# Sheet1.net
KiCad netlist of a schematic drawn in Altium Designer
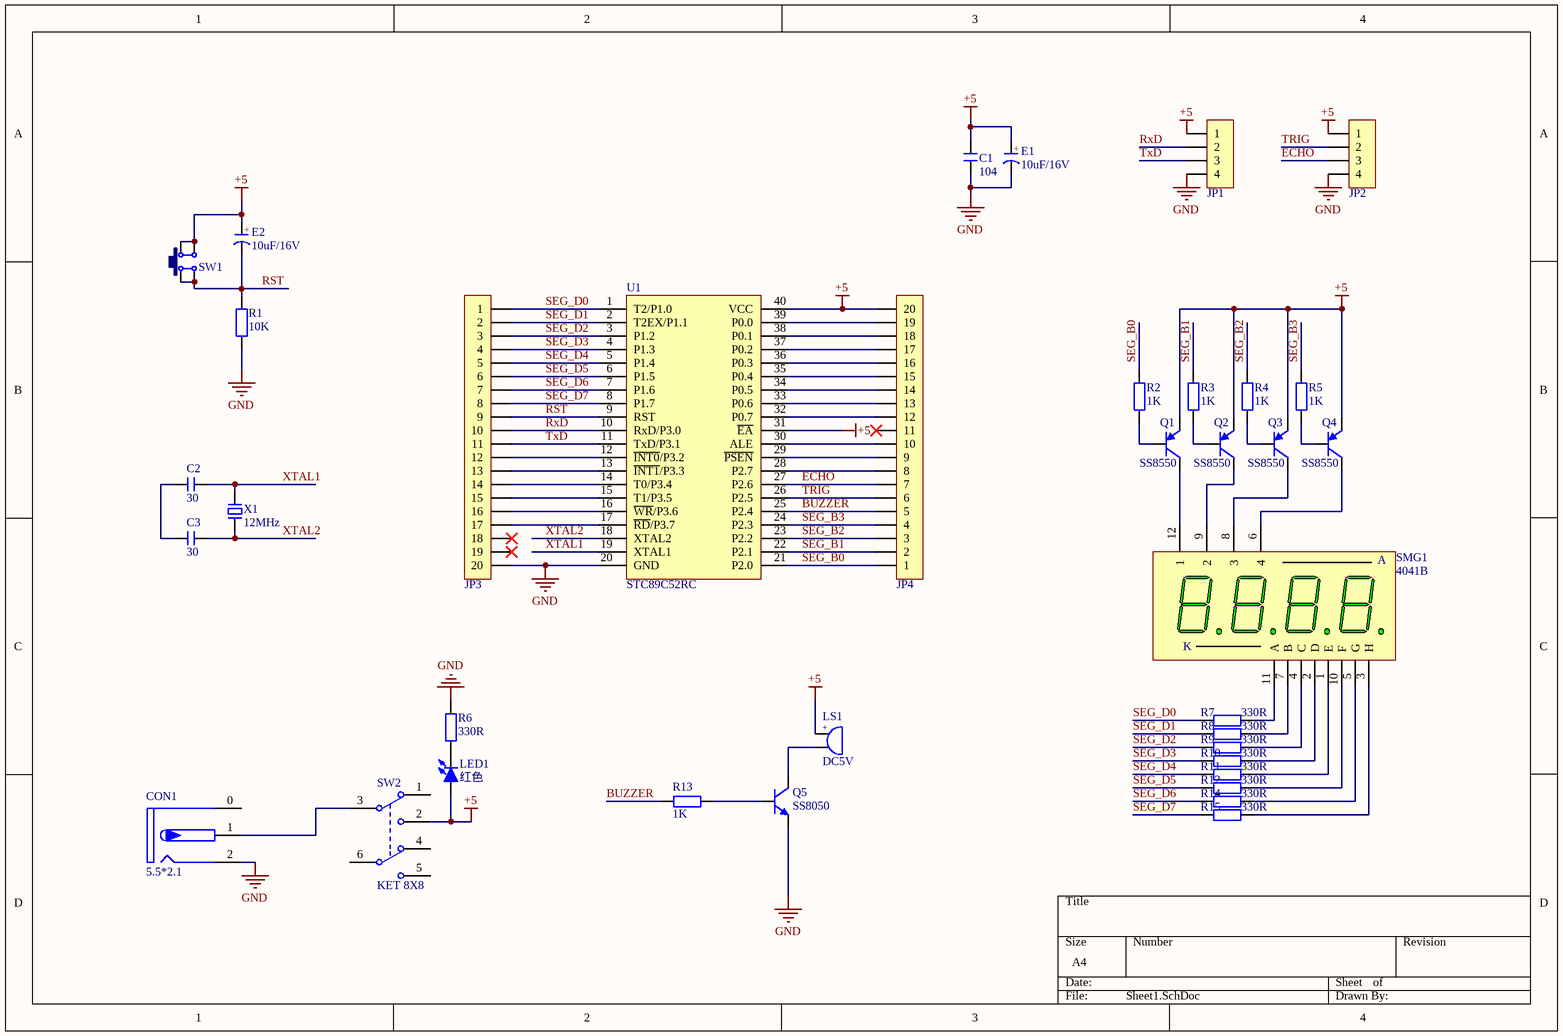
[diagram p0: Sheet1.SchDoc]

(export (version "E")
  (design (tool "Eeschema 10.0.6"))
  (components
    (comp (ref "C1")
      (value "104")
      (footprint "C 0805_M")
      (description "无极性贴片电容")
      (fields (field (name "版权归属") "源创客"))
      (libsource (lib "Schlib1") (part "C"))
    )
    (comp (ref "C2")
      (value "30")
      (footprint "CC 2.2*5")
      (description "直插瓷片电容")
      (fields (field (name "版权归属") "源创客"))
      (libsource (lib "Schlib1") (part "C-CC"))
    )
    (comp (ref "C3")
      (value "30")
      (footprint "CC 2.2*5")
      (description "直插瓷片电容")
      (fields (field (name "版权归属") "源创客"))
      (libsource (lib "Schlib1") (part "C-CC"))
    )
    (comp (ref "CON1")
      (value "5.5*2.1")
      (footprint "DC-005")
      (description "带屏蔽DC电源接口")
      (fields (field (name "版权归属") "源创客"))
      (libsource (lib "Schlib1") (part "DC-005P"))
    )
    (comp (ref "E1")
      (value "10uF/16V")
      (footprint "CAP 3.5*8*11.5")
      (description "直插电解电容")
      (fields (field (name "版权归属") "源创客"))
      (libsource (lib "Schlib1") (part "C-CAP"))
    )
    (comp (ref "E2")
      (value "10uF/16V")
      (footprint "CAP 2.0*5*11 - GD")
      (description "直插电解电容")
      (fields (field (name "版权归属") "源创客"))
      (libsource (lib "Schlib1") (part "C-CAP"))
    )
    (comp (ref "JP1")
      (value "HDR-1X4")
      (footprint "HDR2.54-LI-4P")
      (description "4P接插件")
      (fields (field (name "版权归属") "源创客"))
      (libsource (lib "Schlib1") (part "Header 4"))
    )
    (comp (ref "JP2")
      (value "HDR-1X4")
      (footprint "HDR2.54-LI-4P")
      (description "4P接插件")
      (fields (field (name "版权归属") "源创客"))
      (libsource (lib "Schlib1") (part "Header 4"))
    )
    (comp (ref "JP3")
      (value "HDR-1X20")
      (footprint "HDR2.54-M-LI-20P")
      (description "20P接插件")
      (fields (field (name "版权归属") "源创客"))
      (libsource (lib "") (part "Header 20_1"))
    )
    (comp (ref "JP4")
      (value "HDR-1X20")
      (footprint "HDR2.54-M-LI-20P")
      (description "20P接插件")
      (fields (field (name "版权归属") "源创客"))
      (libsource (lib "Schlib1") (part "Header 20"))
    )
    (comp (ref "LED1")
      (value "红色")
      (footprint "LED 5MM-R")
      (description "5mm插件LED")
      (fields (field (name "版权归属") "源创客"))
      (libsource (lib "Schlib1") (part "LED-5MM"))
    )
    (comp (ref "LS1")
      (value "DC5V")
      (footprint "BEEP 7.6X12X9.5")
      (description "蜂鸣器")
      (fields (field (name "版权归属") "源创客"))
      (libsource (lib "Schlib1") (part "BEEP"))
    )
    (comp (ref "Q1")
      (value "SS8550")
      (footprint "SOT23-3M")
      (description "高频放大-PNP型")
      (fields (field (name "版权归属") "源创客"))
      (libsource (lib "Schlib1") (part "8550-SMD"))
    )
    (comp (ref "Q2")
      (value "SS8550")
      (footprint "SOT23-3M")
      (description "高频放大-PNP型")
      (fields (field (name "版权归属") "源创客"))
      (libsource (lib "Schlib1") (part "8550-SMD"))
    )
    (comp (ref "Q3")
      (value "SS8550")
      (footprint "SOT23-3M")
      (description "高频放大-PNP型")
      (fields (field (name "版权归属") "源创客"))
      (libsource (lib "Schlib1") (part "8550-SMD"))
    )
    (comp (ref "Q4")
      (value "SS8550")
      (footprint "SOT23-3M")
      (description "高频放大-PNP型")
      (fields (field (name "版权归属") "源创客"))
      (libsource (lib "Schlib1") (part "8550-SMD"))
    )
    (comp (ref "Q5")
      (value "SS8050")
      (footprint "TO92A")
      (description "高频放大-NPN型")
      (fields (field (name "版权归属") "源创客"))
      (libsource (lib "Schlib1") (part "8050-DIP"))
    )
    (comp (ref "R1")
      (value "10K")
      (footprint "RS 1/4W")
      (description "直插色环电阻")
      (fields (field (name "版权归属") "源创客"))
      (libsource (lib "Schlib1") (part "R-CRR"))
    )
    (comp (ref "R2")
      (value "1K")
      (footprint "RS 1/4W")
      (description "直插色环电阻")
      (fields (field (name "版权归属") "源创客"))
      (libsource (lib "Schlib1") (part "R-CRR"))
    )
    (comp (ref "R3")
      (value "1K")
      (footprint "RS 1/4W")
      (description "直插色环电阻")
      (fields (field (name "版权归属") "源创客"))
      (libsource (lib "Schlib1") (part "R-CRR"))
    )
    (comp (ref "R4")
      (value "1K")
      (footprint "RS 1/4W")
      (description "直插色环电阻")
      (fields (field (name "版权归属") "源创客"))
      (libsource (lib "Schlib1") (part "R-CRR"))
    )
    (comp (ref "R5")
      (value "1K")
      (footprint "RS 1/4W")
      (description "直插色环电阻")
      (fields (field (name "版权归属") "源创客"))
      (libsource (lib "Schlib1") (part "R-CRR"))
    )
    (comp (ref "R6")
      (value "330R")
      (footprint "RS 1/4W")
      (description "直插色环电阻")
      (fields (field (name "版权归属") "源创客"))
      (libsource (lib "Schlib1") (part "R-CRR"))
    )
    (comp (ref "R7")
      (value "330R")
      (footprint "RS 1/4W")
      (description "直插色环电阻")
      (fields (field (name "版权归属") "源创客"))
      (libsource (lib "Schlib1") (part "R-CRR"))
    )
    (comp (ref "R8")
      (value "330R")
      (footprint "RS 1/4W")
      (description "直插色环电阻")
      (fields (field (name "版权归属") "源创客"))
      (libsource (lib "Schlib1") (part "R-CRR"))
    )
    (comp (ref "R9")
      (value "330R")
      (footprint "RS 1/4W")
      (description "直插色环电阻")
      (fields (field (name "版权归属") "源创客"))
      (libsource (lib "Schlib1") (part "R-CRR"))
    )
    (comp (ref "R10")
      (value "330R")
      (footprint "RS 1/4W")
      (description "直插色环电阻")
      (fields (field (name "版权归属") "源创客"))
      (libsource (lib "Schlib1") (part "R-CRR"))
    )
    (comp (ref "R11")
      (value "330R")
      (footprint "RS 1/4W")
      (description "直插色环电阻")
      (fields (field (name "版权归属") "源创客"))
      (libsource (lib "Schlib1") (part "R-CRR"))
    )
    (comp (ref "R12")
      (value "330R")
      (footprint "RS 1/4W")
      (description "直插色环电阻")
      (fields (field (name "版权归属") "源创客"))
      (libsource (lib "Schlib1") (part "R-CRR"))
    )
    (comp (ref "R13")
      (value "1K")
      (footprint "RS 1/4W")
      (description "直插色环电阻")
      (fields (field (name "版权归属") "源创客"))
      (libsource (lib "Schlib1") (part "R-CRR"))
    )
    (comp (ref "R14")
      (value "330R")
      (footprint "RS 1/4W")
      (description "直插色环电阻")
      (fields (field (name "版权归属") "源创客"))
      (libsource (lib "Schlib1") (part "R-CRR"))
    )
    (comp (ref "R15")
      (value "330R")
      (footprint "RS 1/4W")
      (description "直插色环电阻")
      (fields (field (name "版权归属") "源创客"))
      (libsource (lib "Schlib1") (part "R-CRR"))
    )
    (comp (ref "SMG1")
      (value "4041B")
      (footprint "SMG 0.4-4P")
      (description "0.4寸4位共阳数码管")
      (fields (field (name "版权归属") "源创客"))
      (libsource (lib "Schlib1") (part "4041B"))
    )
    (comp (ref "SW1")
      (value "6x6x5")
      (footprint "TSW DIP-6*6*5")
      (description "直插6x6轻触开关")
      (fields (field (name "版权归属") "源创客"))
      (libsource (lib "Schlib1") (part "TSW DIP-6x6"))
    )
    (comp (ref "SW2")
      (value "KET 8X8")
      (footprint "KFT DIP-8X8")
      (description "8*8自锁开关")
      (fields (field (name "版权归属") "源创客"))
      (libsource (lib "Schlib1") (part "KET 8X8"))
    )
    (comp (ref "U1")
      (value "STC89C52RC")
      (footprint "DIP40-600")
      (description "STC单片机")
      (fields (field (name "版权归属") "源创客"))
      (libsource (lib "Schlib1") (part "STC89C52RC"))
    )
    (comp (ref "X1")
      (value "12MHz")
      (footprint "OSC HC-49S")
      (description "2脚无源脚晶振")
      (fields (field (name "版权归属") "源创客"))
      (libsource (lib "Schlib1") (part "XTAL-2P"))
    )
  )
  (nets
    (net (code "1") (name "+5") (class "Default")
      (node (ref "C1") (pin "2") (pinfunction "2_2") (pintype "passive"))
      (node (ref "E1") (pin "1") (pinfunction "A_1") (pintype "passive"))
      (node (ref "E2") (pin "1") (pinfunction "A_1") (pintype "passive"))
      (node (ref "JP1") (pin "1") (pinfunction "1_1") (pintype "passive"))
      (node (ref "JP2") (pin "1") (pinfunction "1_1") (pintype "passive"))
      (node (ref "JP4") (pin "20") (pinfunction "20_20") (pintype "passive"))
      (node (ref "LED1") (pin "1") (pinfunction "A_1") (pintype "passive"))
      (node (ref "LS1") (pin "1") (pinfunction "1_1") (pintype "passive"))
      (node (ref "Q1") (pin "2") (pinfunction "E_2") (pintype "passive"))
      (node (ref "Q2") (pin "2") (pinfunction "E_2") (pintype "passive"))
      (node (ref "Q3") (pin "2") (pinfunction "E_2") (pintype "passive"))
      (node (ref "Q4") (pin "2") (pinfunction "E_2") (pintype "passive"))
      (node (ref "SW1") (pin "2") (pinfunction "2_2") (pintype "passive"))
      (node (ref "SW1") (pin "3") (pinfunction "3_3") (pintype "passive"))
      (node (ref "SW2") (pin "2") (pinfunction "COM2_2") (pintype "passive"))
      (node (ref "U1") (pin "31") (pinfunction "~{EA}_31") (pintype "passive"))
      (node (ref "U1") (pin "40") (pinfunction "VCC_40") (pintype "passive"))
    )
    (net (code "2") (name "/BUZZER") (class "Default")
      (node (ref "JP4") (pin "5") (pinfunction "5_5") (pintype "passive"))
      (node (ref "R13") (pin "1") (pinfunction "1_1") (pintype "passive"))
      (node (ref "U1") (pin "25") (pinfunction "P2.4_25") (pintype "passive"))
    )
    (net (code "3") (name "/ECHO") (class "Default")
      (node (ref "JP2") (pin "3") (pinfunction "3_3") (pintype "passive"))
      (node (ref "JP4") (pin "7") (pinfunction "7_7") (pintype "passive"))
      (node (ref "U1") (pin "27") (pinfunction "P2.6_27") (pintype "passive"))
    )
    (net (code "4") (name "/RST") (class "Default")
      (node (ref "E2") (pin "2") (pinfunction "K_2") (pintype "passive"))
      (node (ref "JP3") (pin "9") (pinfunction "9_9") (pintype "passive"))
      (node (ref "R1") (pin "2") (pinfunction "2_2") (pintype "passive"))
      (node (ref "SW1") (pin "1") (pinfunction "1_1") (pintype "passive"))
      (node (ref "SW1") (pin "4") (pinfunction "4_4") (pintype "passive"))
      (node (ref "U1") (pin "9") (pinfunction "RST_9") (pintype "passive"))
    )
    (net (code "5") (name "/RxD") (class "Default")
      (node (ref "JP1") (pin "2") (pinfunction "2_2") (pintype "passive"))
      (node (ref "JP3") (pin "10") (pinfunction "10_10") (pintype "passive"))
      (node (ref "U1") (pin "10") (pinfunction "RxD/P3.0_10") (pintype "passive"))
    )
    (net (code "6") (name "/SEG_B0") (class "Default")
      (node (ref "JP4") (pin "1") (pinfunction "1_1") (pintype "passive"))
      (node (ref "R2") (pin "2") (pinfunction "2_2") (pintype "passive"))
      (node (ref "U1") (pin "21") (pinfunction "P2.0_21") (pintype "passive"))
    )
    (net (code "7") (name "/SEG_B1") (class "Default")
      (node (ref "JP4") (pin "2") (pinfunction "2_2") (pintype "passive"))
      (node (ref "R3") (pin "2") (pinfunction "2_2") (pintype "passive"))
      (node (ref "U1") (pin "22") (pinfunction "P2.1_22") (pintype "passive"))
    )
    (net (code "8") (name "/SEG_B2") (class "Default")
      (node (ref "JP4") (pin "3") (pinfunction "3_3") (pintype "passive"))
      (node (ref "R4") (pin "2") (pinfunction "2_2") (pintype "passive"))
      (node (ref "U1") (pin "23") (pinfunction "P2.2_23") (pintype "passive"))
    )
    (net (code "9") (name "/SEG_B3") (class "Default")
      (node (ref "JP4") (pin "4") (pinfunction "4_4") (pintype "passive"))
      (node (ref "R5") (pin "2") (pinfunction "2_2") (pintype "passive"))
      (node (ref "U1") (pin "24") (pinfunction "P2.3_24") (pintype "passive"))
    )
    (net (code "10") (name "/SEG_D0") (class "Default")
      (node (ref "JP3") (pin "1") (pinfunction "1_1") (pintype "passive"))
      (node (ref "R7") (pin "1") (pinfunction "1_1") (pintype "passive"))
      (node (ref "U1") (pin "1") (pinfunction "T2/P1.0_1") (pintype "passive"))
    )
    (net (code "11") (name "/SEG_D1") (class "Default")
      (node (ref "JP3") (pin "2") (pinfunction "2_2") (pintype "passive"))
      (node (ref "R8") (pin "1") (pinfunction "1_1") (pintype "passive"))
      (node (ref "U1") (pin "2") (pinfunction "T2EX/P1.1_2") (pintype "passive"))
    )
    (net (code "12") (name "/SEG_D2") (class "Default")
      (node (ref "JP3") (pin "3") (pinfunction "3_3") (pintype "passive"))
      (node (ref "R9") (pin "1") (pinfunction "1_1") (pintype "passive"))
      (node (ref "U1") (pin "3") (pinfunction "P1.2_3") (pintype "passive"))
    )
    (net (code "13") (name "/SEG_D3") (class "Default")
      (node (ref "JP3") (pin "4") (pinfunction "4_4") (pintype "passive"))
      (node (ref "R10") (pin "1") (pinfunction "1_1") (pintype "passive"))
      (node (ref "U1") (pin "4") (pinfunction "P1.3_4") (pintype "passive"))
    )
    (net (code "14") (name "/SEG_D4") (class "Default")
      (node (ref "JP3") (pin "5") (pinfunction "5_5") (pintype "passive"))
      (node (ref "R11") (pin "1") (pinfunction "1_1") (pintype "passive"))
      (node (ref "U1") (pin "5") (pinfunction "P1.4_5") (pintype "passive"))
    )
    (net (code "15") (name "/SEG_D5") (class "Default")
      (node (ref "JP3") (pin "6") (pinfunction "6_6") (pintype "passive"))
      (node (ref "R12") (pin "1") (pinfunction "1_1") (pintype "passive"))
      (node (ref "U1") (pin "6") (pinfunction "P1.5_6") (pintype "passive"))
    )
    (net (code "16") (name "/SEG_D6") (class "Default")
      (node (ref "JP3") (pin "7") (pinfunction "7_7") (pintype "passive"))
      (node (ref "R14") (pin "1") (pinfunction "1_1") (pintype "passive"))
      (node (ref "U1") (pin "7") (pinfunction "P1.6_7") (pintype "passive"))
    )
    (net (code "17") (name "/SEG_D7") (class "Default")
      (node (ref "JP3") (pin "8") (pinfunction "8_8") (pintype "passive"))
      (node (ref "R15") (pin "1") (pinfunction "1_1") (pintype "passive"))
      (node (ref "U1") (pin "8") (pinfunction "P1.7_8") (pintype "passive"))
    )
    (net (code "18") (name "/TRIG") (class "Default")
      (node (ref "JP2") (pin "2") (pinfunction "2_2") (pintype "passive"))
      (node (ref "JP4") (pin "6") (pinfunction "6_6") (pintype "passive"))
      (node (ref "U1") (pin "26") (pinfunction "P2.5_26") (pintype "passive"))
    )
    (net (code "19") (name "/TxD") (class "Default")
      (node (ref "JP1") (pin "3") (pinfunction "3_3") (pintype "passive"))
      (node (ref "JP3") (pin "11") (pinfunction "11_11") (pintype "passive"))
      (node (ref "U1") (pin "11") (pinfunction "TxD/P3.1_11") (pintype "passive"))
    )
    (net (code "20") (name "/XTAL1") (class "Default")
      (node (ref "C2") (pin "2") (pinfunction "2_2") (pintype "passive"))
      (node (ref "U1") (pin "19") (pinfunction "XTAL1_19") (pintype "passive"))
      (node (ref "X1") (pin "2") (pinfunction "2_2") (pintype "passive"))
    )
    (net (code "21") (name "/XTAL2") (class "Default")
      (node (ref "C3") (pin "2") (pinfunction "2_2") (pintype "passive"))
      (node (ref "U1") (pin "18") (pinfunction "XTAL2_18") (pintype "passive"))
      (node (ref "X1") (pin "1") (pinfunction "1_1") (pintype "passive"))
    )
    (net (code "22") (name "GND") (class "Default")
      (node (ref "C1") (pin "1") (pinfunction "1_1") (pintype "passive"))
      (node (ref "CON1") (pin "2") (pintype "power_in"))
      (node (ref "E1") (pin "2") (pinfunction "K_2") (pintype "passive"))
      (node (ref "JP1") (pin "4") (pinfunction "4_4") (pintype "passive"))
      (node (ref "JP2") (pin "4") (pinfunction "4_4") (pintype "passive"))
      (node (ref "JP3") (pin "20") (pinfunction "20_20") (pintype "passive"))
      (node (ref "Q5") (pin "1") (pinfunction "E_1") (pintype "passive"))
      (node (ref "R1") (pin "1") (pinfunction "1_1") (pintype "passive"))
      (node (ref "R6") (pin "2") (pinfunction "2_2") (pintype "passive"))
      (node (ref "U1") (pin "20") (pinfunction "GND_20") (pintype "passive"))
    )
    (net (code "23") (name "Net-(C2-Pad1)") (class "Default")
      (node (ref "C2") (pin "1") (pinfunction "1_1") (pintype "passive"))
      (node (ref "C3") (pin "1") (pinfunction "1_1") (pintype "passive"))
    )
    (net (code "24") (name "Net-(LED1-K)") (class "Default")
      (node (ref "LED1") (pin "2") (pinfunction "K_2") (pintype "passive"))
      (node (ref "R6") (pin "1") (pinfunction "1_1") (pintype "passive"))
    )
    (net (code "25") (name "Net-(Q1-B)") (class "Default")
      (node (ref "Q1") (pin "1") (pinfunction "B_1") (pintype "passive"))
      (node (ref "R2") (pin "1") (pinfunction "1_1") (pintype "passive"))
    )
    (net (code "26") (name "Net-(Q1-C)") (class "Default")
      (node (ref "Q1") (pin "3") (pinfunction "C_3") (pintype "passive"))
      (node (ref "SMG1") (pin "12") (pinfunction "1_12") (pintype "passive"))
    )
    (net (code "27") (name "Net-(Q2-B)") (class "Default")
      (node (ref "Q2") (pin "1") (pinfunction "B_1") (pintype "passive"))
      (node (ref "R3") (pin "1") (pinfunction "1_1") (pintype "passive"))
    )
    (net (code "28") (name "Net-(Q2-C)") (class "Default")
      (node (ref "Q2") (pin "3") (pinfunction "C_3") (pintype "passive"))
      (node (ref "SMG1") (pin "9") (pinfunction "2_9") (pintype "passive"))
    )
    (net (code "29") (name "Net-(Q3-B)") (class "Default")
      (node (ref "Q3") (pin "1") (pinfunction "B_1") (pintype "passive"))
      (node (ref "R4") (pin "1") (pinfunction "1_1") (pintype "passive"))
    )
    (net (code "30") (name "Net-(Q3-C)") (class "Default")
      (node (ref "Q3") (pin "3") (pinfunction "C_3") (pintype "passive"))
      (node (ref "SMG1") (pin "8") (pinfunction "3_8") (pintype "passive"))
    )
    (net (code "31") (name "Net-(Q4-B)") (class "Default")
      (node (ref "Q4") (pin "1") (pinfunction "B_1") (pintype "passive"))
      (node (ref "R5") (pin "1") (pinfunction "1_1") (pintype "passive"))
    )
    (net (code "32") (name "Net-(Q4-C)") (class "Default")
      (node (ref "Q4") (pin "3") (pinfunction "C_3") (pintype "passive"))
      (node (ref "SMG1") (pin "6") (pinfunction "4_6") (pintype "passive"))
    )
    (net (code "33") (name "Net-(Q5-B)") (class "Default")
      (node (ref "Q5") (pin "2") (pinfunction "B_2") (pintype "passive"))
      (node (ref "R13") (pin "2") (pinfunction "2_2") (pintype "passive"))
    )
    (net (code "34") (name "Net-(Q5-C)") (class "Default")
      (node (ref "LS1") (pin "2") (pinfunction "2_2") (pintype "passive"))
      (node (ref "Q5") (pin "3") (pinfunction "C_3") (pintype "passive"))
    )
    (net (code "35") (name "Net-(SMG1-A)") (class "Default")
      (node (ref "R7") (pin "2") (pinfunction "2_2") (pintype "passive"))
      (node (ref "SMG1") (pin "11") (pinfunction "A_11") (pintype "passive"))
    )
    (net (code "36") (name "Net-(SMG1-B)") (class "Default")
      (node (ref "R8") (pin "2") (pinfunction "2_2") (pintype "passive"))
      (node (ref "SMG1") (pin "7") (pinfunction "B_7") (pintype "passive"))
    )
    (net (code "37") (name "Net-(SMG1-C)") (class "Default")
      (node (ref "R9") (pin "2") (pinfunction "2_2") (pintype "passive"))
      (node (ref "SMG1") (pin "4") (pinfunction "C_4") (pintype "passive"))
    )
    (net (code "38") (name "Net-(SMG1-D)") (class "Default")
      (node (ref "R10") (pin "2") (pinfunction "2_2") (pintype "passive"))
      (node (ref "SMG1") (pin "2") (pinfunction "D_2") (pintype "passive"))
    )
    (net (code "39") (name "Net-(SMG1-E)") (class "Default")
      (node (ref "R11") (pin "2") (pinfunction "2_2") (pintype "passive"))
      (node (ref "SMG1") (pin "1") (pinfunction "E_1") (pintype "passive"))
    )
    (net (code "40") (name "Net-(SMG1-F)") (class "Default")
      (node (ref "R12") (pin "2") (pinfunction "2_2") (pintype "passive"))
      (node (ref "SMG1") (pin "10") (pinfunction "F_10") (pintype "passive"))
    )
    (net (code "41") (name "Net-(SMG1-G)") (class "Default")
      (node (ref "R14") (pin "2") (pinfunction "2_2") (pintype "passive"))
      (node (ref "SMG1") (pin "5") (pinfunction "G_5") (pintype "passive"))
    )
    (net (code "42") (name "Net-(SMG1-H)") (class "Default")
      (node (ref "R15") (pin "2") (pinfunction "2_2") (pintype "passive"))
      (node (ref "SMG1") (pin "3") (pinfunction "H_3") (pintype "passive"))
    )
    (net (code "43") (name "Net-(SW2-NO1)") (class "Default")
      (node (ref "CON1") (pin "1") (pintype "power_in"))
      (node (ref "SW2") (pin "3") (pinfunction "NO1_3") (pintype "passive"))
    )
    (net (code "44") (name "Net-(U1-ALE)") (class "Default")
      (node (ref "JP4") (pin "10") (pinfunction "10_10") (pintype "passive"))
      (node (ref "U1") (pin "30") (pinfunction "ALE_30") (pintype "passive"))
    )
    (net (code "45") (name "Net-(U1-P0.0)") (class "Default")
      (node (ref "JP4") (pin "19") (pinfunction "19_19") (pintype "passive"))
      (node (ref "U1") (pin "39") (pinfunction "P0.0_39") (pintype "passive"))
    )
    (net (code "46") (name "Net-(U1-P0.1)") (class "Default")
      (node (ref "JP4") (pin "18") (pinfunction "18_18") (pintype "passive"))
      (node (ref "U1") (pin "38") (pinfunction "P0.1_38") (pintype "passive"))
    )
    (net (code "47") (name "Net-(U1-P0.2)") (class "Default")
      (node (ref "JP4") (pin "17") (pinfunction "17_17") (pintype "passive"))
      (node (ref "U1") (pin "37") (pinfunction "P0.2_37") (pintype "passive"))
    )
    (net (code "48") (name "Net-(U1-P0.3)") (class "Default")
      (node (ref "JP4") (pin "16") (pinfunction "16_16") (pintype "passive"))
      (node (ref "U1") (pin "36") (pinfunction "P0.3_36") (pintype "passive"))
    )
    (net (code "49") (name "Net-(U1-P0.4)") (class "Default")
      (node (ref "JP4") (pin "15") (pinfunction "15_15") (pintype "passive"))
      (node (ref "U1") (pin "35") (pinfunction "P0.4_35") (pintype "passive"))
    )
    (net (code "50") (name "Net-(U1-P0.5)") (class "Default")
      (node (ref "JP4") (pin "14") (pinfunction "14_14") (pintype "passive"))
      (node (ref "U1") (pin "34") (pinfunction "P0.5_34") (pintype "passive"))
    )
    (net (code "51") (name "Net-(U1-P0.6)") (class "Default")
      (node (ref "JP4") (pin "13") (pinfunction "13_13") (pintype "passive"))
      (node (ref "U1") (pin "33") (pinfunction "P0.6_33") (pintype "passive"))
    )
    (net (code "52") (name "Net-(U1-P0.7)") (class "Default")
      (node (ref "JP4") (pin "12") (pinfunction "12_12") (pintype "passive"))
      (node (ref "U1") (pin "32") (pinfunction "P0.7_32") (pintype "passive"))
    )
    (net (code "53") (name "Net-(U1-P2.7)") (class "Default")
      (node (ref "JP4") (pin "8") (pinfunction "8_8") (pintype "passive"))
      (node (ref "U1") (pin "28") (pinfunction "P2.7_28") (pintype "passive"))
    )
    (net (code "54") (name "Net-(U1-T0{slash}P3.4)") (class "Default")
      (node (ref "JP3") (pin "14") (pinfunction "14_14") (pintype "passive"))
      (node (ref "U1") (pin "14") (pinfunction "T0/P3.4_14") (pintype "passive"))
    )
    (net (code "55") (name "Net-(U1-T1{slash}P3.5)") (class "Default")
      (node (ref "JP3") (pin "15") (pinfunction "15_15") (pintype "passive"))
      (node (ref "U1") (pin "15") (pinfunction "T1/P3.5_15") (pintype "passive"))
    )
    (net (code "56") (name "Net-(U1-~{INT0}{slash}P3.2)") (class "Default")
      (node (ref "JP3") (pin "12") (pinfunction "12_12") (pintype "passive"))
      (node (ref "U1") (pin "12") (pinfunction "~{INT0}/P3.2_12") (pintype "passive"))
    )
    (net (code "57") (name "Net-(U1-~{INT1}{slash}P3.3)") (class "Default")
      (node (ref "JP3") (pin "13") (pinfunction "13_13") (pintype "passive"))
      (node (ref "U1") (pin "13") (pinfunction "~{INT1}/P3.3_13") (pintype "passive"))
    )
    (net (code "58") (name "Net-(U1-~{PSEN})") (class "Default")
      (node (ref "JP4") (pin "9") (pinfunction "9_9") (pintype "passive"))
      (node (ref "U1") (pin "29") (pinfunction "~{PSEN}_29") (pintype "passive"))
    )
    (net (code "59") (name "Net-(U1-~{RD}{slash}P3.7)") (class "Default")
      (node (ref "JP3") (pin "17") (pinfunction "17_17") (pintype "passive"))
      (node (ref "U1") (pin "17") (pinfunction "~{RD}/P3.7_17") (pintype "passive"))
    )
    (net (code "60") (name "Net-(U1-~{WR}{slash}P3.6)") (class "Default")
      (node (ref "JP3") (pin "16") (pinfunction "16_16") (pintype "passive"))
      (node (ref "U1") (pin "16") (pinfunction "~{WR}/P3.6_16") (pintype "passive"))
    )
    (net (code "61") (name "unconnected-(CON1-Pad0)") (class "Default")
      (node (ref "CON1") (pin "0") (pintype "power_in"))
    )
    (net (code "62") (name "unconnected-(JP3-Pad18)") (class "Default")
      (node (ref "JP3") (pin "18") (pinfunction "18_18") (pintype "passive+no_connect"))
    )
    (net (code "63") (name "unconnected-(JP3-Pad19)") (class "Default")
      (node (ref "JP3") (pin "19") (pinfunction "19_19") (pintype "passive+no_connect"))
    )
    (net (code "64") (name "unconnected-(JP4-Pad11)") (class "Default")
      (node (ref "JP4") (pin "11") (pinfunction "11_11") (pintype "passive+no_connect"))
    )
    (net (code "65") (name "unconnected-(SW2-COM2-Pad5)") (class "Default")
      (node (ref "SW2") (pin "5") (pinfunction "COM2_5") (pintype "passive"))
    )
    (net (code "66") (name "unconnected-(SW2-NC1-Pad1)") (class "Default")
      (node (ref "SW2") (pin "1") (pinfunction "NC1_1") (pintype "passive"))
    )
    (net (code "67") (name "unconnected-(SW2-NC2-Pad6)") (class "Default")
      (node (ref "SW2") (pin "6") (pinfunction "NC2_6") (pintype "passive"))
    )
    (net (code "68") (name "unconnected-(SW2-NO2-Pad4)") (class "Default")
      (node (ref "SW2") (pin "4") (pinfunction "NO2_4") (pintype "passive"))
    )
  )
)
